# QDRII_power.net
KiCad netlist of a schematic drawn in Altium Designer
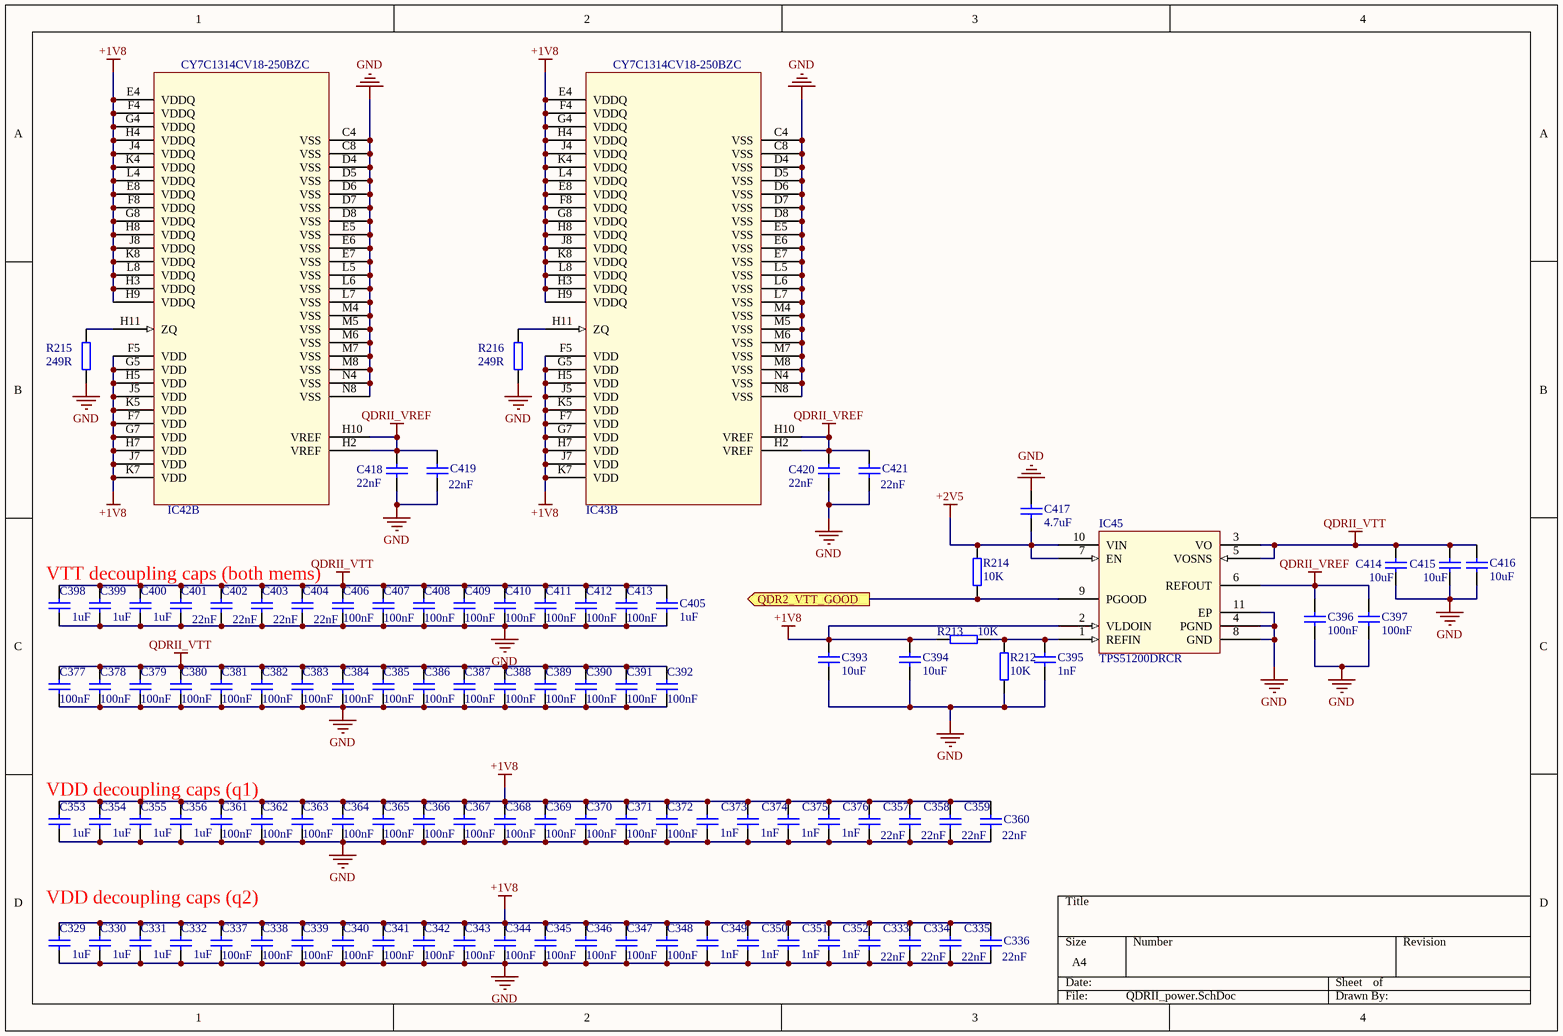
[diagram p0: QDRII_power.SchDoc]

(export (version "E")
  (design (tool "Eeschema 10.0.6"))
  (components
    (comp (ref "C329")
      (value "1uF")
      (footprint "CC1005-0402")
      (description "Capacitor")
      (fields
        (field (name "TOLERANCE") "±10%")
        (field (name "VOLTAGE") "16V")
        (field (name "PUBLISHER") "Altium Limited")
      )
      (libsource (lib "wr_switch") (part "Cap"))
    )
    (comp (ref "C330")
      (value "1uF")
      (footprint "CC1005-0402")
      (description "Capacitor")
      (fields
        (field (name "TOLERANCE") "±10%")
        (field (name "VOLTAGE") "16V")
        (field (name "PUBLISHER") "Altium Limited")
      )
      (libsource (lib "wr_switch") (part "Cap"))
    )
    (comp (ref "C331")
      (value "1uF")
      (footprint "CC1005-0402")
      (description "Capacitor")
      (fields
        (field (name "TOLERANCE") "±10%")
        (field (name "VOLTAGE") "16V")
        (field (name "PUBLISHER") "Altium Limited")
      )
      (libsource (lib "wr_switch") (part "Cap"))
    )
    (comp (ref "C332")
      (value "1uF")
      (footprint "CC1005-0402")
      (description "Capacitor")
      (fields
        (field (name "TOLERANCE") "±10%")
        (field (name "VOLTAGE") "16V")
        (field (name "PUBLISHER") "Altium Limited")
      )
      (libsource (lib "wr_switch") (part "Cap"))
    )
    (comp (ref "C333")
      (value "22nF")
      (footprint "CC1005-0402")
      (description "Capacitor")
      (fields
        (field (name "TOLERANCE") "±10%")
        (field (name "VOLTAGE") "25V")
        (field (name "PUBLISHER") "Altium Limited")
      )
      (libsource (lib "wr_switch") (part "Cap"))
    )
    (comp (ref "C334")
      (value "22nF")
      (footprint "CC1005-0402")
      (description "Capacitor")
      (fields
        (field (name "TOLERANCE") "±10%")
        (field (name "VOLTAGE") "25V")
        (field (name "PUBLISHER") "Altium Limited")
      )
      (libsource (lib "wr_switch") (part "Cap"))
    )
    (comp (ref "C335")
      (value "22nF")
      (footprint "CC1005-0402")
      (description "Capacitor")
      (fields
        (field (name "TOLERANCE") "±10%")
        (field (name "VOLTAGE") "25V")
        (field (name "PUBLISHER") "Altium Limited")
      )
      (libsource (lib "wr_switch") (part "Cap"))
    )
    (comp (ref "C336")
      (value "22nF")
      (footprint "CC1005-0402")
      (description "Capacitor")
      (fields
        (field (name "TOLERANCE") "±10%")
        (field (name "VOLTAGE") "25V")
        (field (name "PUBLISHER") "Altium Limited")
      )
      (libsource (lib "wr_switch") (part "Cap"))
    )
    (comp (ref "C337")
      (value "100nF")
      (footprint "CC1005-0402")
      (description "Capacitor")
      (fields
        (field (name "TOLERANCE") "±10%")
        (field (name "VOLTAGE") "16V")
        (field (name "PUBLISHER") "Altium Limited")
      )
      (libsource (lib "wr_switch") (part "Cap"))
    )
    (comp (ref "C338")
      (value "100nF")
      (footprint "CC1005-0402")
      (description "Capacitor")
      (fields
        (field (name "TOLERANCE") "±10%")
        (field (name "VOLTAGE") "16V")
        (field (name "PUBLISHER") "Altium Limited")
      )
      (libsource (lib "wr_switch") (part "Cap"))
    )
    (comp (ref "C339")
      (value "100nF")
      (footprint "CC1005-0402")
      (description "Capacitor")
      (fields
        (field (name "TOLERANCE") "±10%")
        (field (name "VOLTAGE") "16V")
        (field (name "PUBLISHER") "Altium Limited")
      )
      (libsource (lib "wr_switch") (part "Cap"))
    )
    (comp (ref "C340")
      (value "100nF")
      (footprint "CC1005-0402")
      (description "Capacitor")
      (fields
        (field (name "TOLERANCE") "±10%")
        (field (name "VOLTAGE") "16V")
        (field (name "PUBLISHER") "Altium Limited")
      )
      (libsource (lib "wr_switch") (part "Cap"))
    )
    (comp (ref "C341")
      (value "100nF")
      (footprint "CC1005-0402")
      (description "Capacitor")
      (fields
        (field (name "TOLERANCE") "±10%")
        (field (name "VOLTAGE") "16V")
        (field (name "PUBLISHER") "Altium Limited")
      )
      (libsource (lib "wr_switch") (part "Cap"))
    )
    (comp (ref "C342")
      (value "100nF")
      (footprint "CC1005-0402")
      (description "Capacitor")
      (fields
        (field (name "TOLERANCE") "±10%")
        (field (name "VOLTAGE") "16V")
        (field (name "PUBLISHER") "Altium Limited")
      )
      (libsource (lib "wr_switch") (part "Cap"))
    )
    (comp (ref "C343")
      (value "100nF")
      (footprint "CC1005-0402")
      (description "Capacitor")
      (fields
        (field (name "TOLERANCE") "±10%")
        (field (name "VOLTAGE") "16V")
        (field (name "PUBLISHER") "Altium Limited")
      )
      (libsource (lib "wr_switch") (part "Cap"))
    )
    (comp (ref "C344")
      (value "100nF")
      (footprint "CC1005-0402")
      (description "Capacitor")
      (fields
        (field (name "TOLERANCE") "±10%")
        (field (name "VOLTAGE") "16V")
        (field (name "PUBLISHER") "Altium Limited")
      )
      (libsource (lib "wr_switch") (part "Cap"))
    )
    (comp (ref "C345")
      (value "100nF")
      (footprint "CC1005-0402")
      (description "Capacitor")
      (fields
        (field (name "TOLERANCE") "±10%")
        (field (name "VOLTAGE") "16V")
        (field (name "PUBLISHER") "Altium Limited")
      )
      (libsource (lib "wr_switch") (part "Cap"))
    )
    (comp (ref "C346")
      (value "100nF")
      (footprint "CC1005-0402")
      (description "Capacitor")
      (fields
        (field (name "TOLERANCE") "±10%")
        (field (name "VOLTAGE") "16V")
        (field (name "PUBLISHER") "Altium Limited")
      )
      (libsource (lib "wr_switch") (part "Cap"))
    )
    (comp (ref "C347")
      (value "100nF")
      (footprint "CC1005-0402")
      (description "Capacitor")
      (fields
        (field (name "TOLERANCE") "±10%")
        (field (name "VOLTAGE") "16V")
        (field (name "PUBLISHER") "Altium Limited")
      )
      (libsource (lib "wr_switch") (part "Cap"))
    )
    (comp (ref "C348")
      (value "100nF")
      (footprint "CC1005-0402")
      (description "Capacitor")
      (fields
        (field (name "TOLERANCE") "±10%")
        (field (name "VOLTAGE") "16V")
        (field (name "PUBLISHER") "Altium Limited")
      )
      (libsource (lib "wr_switch") (part "Cap"))
    )
    (comp (ref "C349")
      (value "1nF")
      (footprint "CC1005-0402")
      (description "Capacitor")
      (fields
        (field (name "TOLERANCE") "±10%")
        (field (name "VOLTAGE") "25V")
        (field (name "PUBLISHER") "Altium Limited")
      )
      (libsource (lib "wr_switch") (part "Cap"))
    )
    (comp (ref "C350")
      (value "1nF")
      (footprint "CC1005-0402")
      (description "Capacitor")
      (fields
        (field (name "TOLERANCE") "±10%")
        (field (name "VOLTAGE") "25V")
        (field (name "PUBLISHER") "Altium Limited")
      )
      (libsource (lib "wr_switch") (part "Cap"))
    )
    (comp (ref "C351")
      (value "1nF")
      (footprint "CC1005-0402")
      (description "Capacitor")
      (fields
        (field (name "TOLERANCE") "±10%")
        (field (name "VOLTAGE") "25V")
        (field (name "PUBLISHER") "Altium Limited")
      )
      (libsource (lib "wr_switch") (part "Cap"))
    )
    (comp (ref "C352")
      (value "1nF")
      (footprint "CC1005-0402")
      (description "Capacitor")
      (fields
        (field (name "TOLERANCE") "±10%")
        (field (name "VOLTAGE") "25V")
        (field (name "PUBLISHER") "Altium Limited")
      )
      (libsource (lib "wr_switch") (part "Cap"))
    )
    (comp (ref "C353")
      (value "1uF")
      (footprint "CC1005-0402")
      (description "Capacitor")
      (fields
        (field (name "TOLERANCE") "±10%")
        (field (name "VOLTAGE") "16V")
        (field (name "PUBLISHER") "Altium Limited")
      )
      (libsource (lib "wr_switch") (part "Cap"))
    )
    (comp (ref "C354")
      (value "1uF")
      (footprint "CC1005-0402")
      (description "Capacitor")
      (fields
        (field (name "TOLERANCE") "±10%")
        (field (name "VOLTAGE") "16V")
        (field (name "PUBLISHER") "Altium Limited")
      )
      (libsource (lib "wr_switch") (part "Cap"))
    )
    (comp (ref "C355")
      (value "1uF")
      (footprint "CC1005-0402")
      (description "Capacitor")
      (fields
        (field (name "TOLERANCE") "±10%")
        (field (name "VOLTAGE") "16V")
        (field (name "PUBLISHER") "Altium Limited")
      )
      (libsource (lib "wr_switch") (part "Cap"))
    )
    (comp (ref "C356")
      (value "1uF")
      (footprint "CC1005-0402")
      (description "Capacitor")
      (fields
        (field (name "TOLERANCE") "±10%")
        (field (name "VOLTAGE") "16V")
        (field (name "PUBLISHER") "Altium Limited")
      )
      (libsource (lib "wr_switch") (part "Cap"))
    )
    (comp (ref "C357")
      (value "22nF")
      (footprint "CC1005-0402")
      (description "Capacitor")
      (fields
        (field (name "TOLERANCE") "±10%")
        (field (name "VOLTAGE") "25V")
        (field (name "PUBLISHER") "Altium Limited")
      )
      (libsource (lib "wr_switch") (part "Cap"))
    )
    (comp (ref "C358")
      (value "22nF")
      (footprint "CC1005-0402")
      (description "Capacitor")
      (fields
        (field (name "TOLERANCE") "±10%")
        (field (name "VOLTAGE") "25V")
        (field (name "PUBLISHER") "Altium Limited")
      )
      (libsource (lib "wr_switch") (part "Cap"))
    )
    (comp (ref "C359")
      (value "22nF")
      (footprint "CC1005-0402")
      (description "Capacitor")
      (fields
        (field (name "TOLERANCE") "±10%")
        (field (name "VOLTAGE") "25V")
        (field (name "PUBLISHER") "Altium Limited")
      )
      (libsource (lib "wr_switch") (part "Cap"))
    )
    (comp (ref "C360")
      (value "22nF")
      (footprint "CC1005-0402")
      (description "Capacitor")
      (fields
        (field (name "TOLERANCE") "±10%")
        (field (name "VOLTAGE") "25V")
        (field (name "PUBLISHER") "Altium Limited")
      )
      (libsource (lib "wr_switch") (part "Cap"))
    )
    (comp (ref "C361")
      (value "100nF")
      (footprint "CC1005-0402")
      (description "Capacitor")
      (fields
        (field (name "TOLERANCE") "±10%")
        (field (name "VOLTAGE") "16V")
        (field (name "PUBLISHER") "Altium Limited")
      )
      (libsource (lib "wr_switch") (part "Cap"))
    )
    (comp (ref "C362")
      (value "100nF")
      (footprint "CC1005-0402")
      (description "Capacitor")
      (fields
        (field (name "TOLERANCE") "±10%")
        (field (name "VOLTAGE") "16V")
        (field (name "PUBLISHER") "Altium Limited")
      )
      (libsource (lib "wr_switch") (part "Cap"))
    )
    (comp (ref "C363")
      (value "100nF")
      (footprint "CC1005-0402")
      (description "Capacitor")
      (fields
        (field (name "TOLERANCE") "±10%")
        (field (name "VOLTAGE") "16V")
        (field (name "PUBLISHER") "Altium Limited")
      )
      (libsource (lib "wr_switch") (part "Cap"))
    )
    (comp (ref "C364")
      (value "100nF")
      (footprint "CC1005-0402")
      (description "Capacitor")
      (fields
        (field (name "TOLERANCE") "±10%")
        (field (name "VOLTAGE") "16V")
        (field (name "PUBLISHER") "Altium Limited")
      )
      (libsource (lib "wr_switch") (part "Cap"))
    )
    (comp (ref "C365")
      (value "100nF")
      (footprint "CC1005-0402")
      (description "Capacitor")
      (fields
        (field (name "TOLERANCE") "±10%")
        (field (name "VOLTAGE") "16V")
        (field (name "PUBLISHER") "Altium Limited")
      )
      (libsource (lib "wr_switch") (part "Cap"))
    )
    (comp (ref "C366")
      (value "100nF")
      (footprint "CC1005-0402")
      (description "Capacitor")
      (fields
        (field (name "TOLERANCE") "±10%")
        (field (name "VOLTAGE") "16V")
        (field (name "PUBLISHER") "Altium Limited")
      )
      (libsource (lib "wr_switch") (part "Cap"))
    )
    (comp (ref "C367")
      (value "100nF")
      (footprint "CC1005-0402")
      (description "Capacitor")
      (fields
        (field (name "TOLERANCE") "±10%")
        (field (name "VOLTAGE") "16V")
        (field (name "PUBLISHER") "Altium Limited")
      )
      (libsource (lib "wr_switch") (part "Cap"))
    )
    (comp (ref "C368")
      (value "100nF")
      (footprint "CC1005-0402")
      (description "Capacitor")
      (fields
        (field (name "TOLERANCE") "±10%")
        (field (name "VOLTAGE") "16V")
        (field (name "PUBLISHER") "Altium Limited")
      )
      (libsource (lib "wr_switch") (part "Cap"))
    )
    (comp (ref "C369")
      (value "100nF")
      (footprint "CC1005-0402")
      (description "Capacitor")
      (fields
        (field (name "TOLERANCE") "±10%")
        (field (name "VOLTAGE") "16V")
        (field (name "PUBLISHER") "Altium Limited")
      )
      (libsource (lib "wr_switch") (part "Cap"))
    )
    (comp (ref "C370")
      (value "100nF")
      (footprint "CC1005-0402")
      (description "Capacitor")
      (fields
        (field (name "TOLERANCE") "±10%")
        (field (name "VOLTAGE") "16V")
        (field (name "PUBLISHER") "Altium Limited")
      )
      (libsource (lib "wr_switch") (part "Cap"))
    )
    (comp (ref "C371")
      (value "100nF")
      (footprint "CC1005-0402")
      (description "Capacitor")
      (fields
        (field (name "TOLERANCE") "±10%")
        (field (name "VOLTAGE") "16V")
        (field (name "PUBLISHER") "Altium Limited")
      )
      (libsource (lib "wr_switch") (part "Cap"))
    )
    (comp (ref "C372")
      (value "100nF")
      (footprint "CC1005-0402")
      (description "Capacitor")
      (fields
        (field (name "TOLERANCE") "±10%")
        (field (name "VOLTAGE") "16V")
        (field (name "PUBLISHER") "Altium Limited")
      )
      (libsource (lib "wr_switch") (part "Cap"))
    )
    (comp (ref "C373")
      (value "1nF")
      (footprint "CC1005-0402")
      (description "Capacitor")
      (fields
        (field (name "TOLERANCE") "±10%")
        (field (name "VOLTAGE") "25V")
        (field (name "PUBLISHER") "Altium Limited")
      )
      (libsource (lib "wr_switch") (part "Cap"))
    )
    (comp (ref "C374")
      (value "1nF")
      (footprint "CC1005-0402")
      (description "Capacitor")
      (fields
        (field (name "TOLERANCE") "±10%")
        (field (name "VOLTAGE") "25V")
        (field (name "PUBLISHER") "Altium Limited")
      )
      (libsource (lib "wr_switch") (part "Cap"))
    )
    (comp (ref "C375")
      (value "1nF")
      (footprint "CC1005-0402")
      (description "Capacitor")
      (fields
        (field (name "TOLERANCE") "±10%")
        (field (name "VOLTAGE") "25V")
        (field (name "PUBLISHER") "Altium Limited")
      )
      (libsource (lib "wr_switch") (part "Cap"))
    )
    (comp (ref "C376")
      (value "1nF")
      (footprint "CC1005-0402")
      (description "Capacitor")
      (fields
        (field (name "TOLERANCE") "±10%")
        (field (name "VOLTAGE") "25V")
        (field (name "PUBLISHER") "Altium Limited")
      )
      (libsource (lib "wr_switch") (part "Cap"))
    )
    (comp (ref "C377")
      (value "100nF")
      (footprint "CC1005-0402")
      (description "Capacitor")
      (fields
        (field (name "TOLERANCE") "±10%")
        (field (name "VOLTAGE") "16V")
        (field (name "PUBLISHER") "Altium Limited")
      )
      (libsource (lib "wr_switch") (part "Cap"))
    )
    (comp (ref "C378")
      (value "100nF")
      (footprint "CC1005-0402")
      (description "Capacitor")
      (fields
        (field (name "TOLERANCE") "±10%")
        (field (name "VOLTAGE") "16V")
        (field (name "PUBLISHER") "Altium Limited")
      )
      (libsource (lib "wr_switch") (part "Cap"))
    )
    (comp (ref "C379")
      (value "100nF")
      (footprint "CC1005-0402")
      (description "Capacitor")
      (fields
        (field (name "TOLERANCE") "±10%")
        (field (name "VOLTAGE") "16V")
        (field (name "PUBLISHER") "Altium Limited")
      )
      (libsource (lib "wr_switch") (part "Cap"))
    )
    (comp (ref "C380")
      (value "100nF")
      (footprint "CC1005-0402")
      (description "Capacitor")
      (fields
        (field (name "TOLERANCE") "±10%")
        (field (name "VOLTAGE") "16V")
        (field (name "PUBLISHER") "Altium Limited")
      )
      (libsource (lib "wr_switch") (part "Cap"))
    )
    (comp (ref "C381")
      (value "100nF")
      (footprint "CC1005-0402")
      (description "Capacitor")
      (fields
        (field (name "TOLERANCE") "±10%")
        (field (name "VOLTAGE") "16V")
        (field (name "PUBLISHER") "Altium Limited")
      )
      (libsource (lib "wr_switch") (part "Cap"))
    )
    (comp (ref "C382")
      (value "100nF")
      (footprint "CC1005-0402")
      (description "Capacitor")
      (fields
        (field (name "TOLERANCE") "±10%")
        (field (name "VOLTAGE") "16V")
        (field (name "PUBLISHER") "Altium Limited")
      )
      (libsource (lib "wr_switch") (part "Cap"))
    )
    (comp (ref "C383")
      (value "100nF")
      (footprint "CC1005-0402")
      (description "Capacitor")
      (fields
        (field (name "TOLERANCE") "±10%")
        (field (name "VOLTAGE") "16V")
        (field (name "PUBLISHER") "Altium Limited")
      )
      (libsource (lib "wr_switch") (part "Cap"))
    )
    (comp (ref "C384")
      (value "100nF")
      (footprint "CC1005-0402")
      (description "Capacitor")
      (fields
        (field (name "TOLERANCE") "±10%")
        (field (name "VOLTAGE") "16V")
        (field (name "PUBLISHER") "Altium Limited")
      )
      (libsource (lib "wr_switch") (part "Cap"))
    )
    (comp (ref "C385")
      (value "100nF")
      (footprint "CC1005-0402")
      (description "Capacitor")
      (fields
        (field (name "TOLERANCE") "±10%")
        (field (name "VOLTAGE") "16V")
        (field (name "PUBLISHER") "Altium Limited")
      )
      (libsource (lib "wr_switch") (part "Cap"))
    )
    (comp (ref "C386")
      (value "100nF")
      (footprint "CC1005-0402")
      (description "Capacitor")
      (fields
        (field (name "TOLERANCE") "±10%")
        (field (name "VOLTAGE") "16V")
        (field (name "PUBLISHER") "Altium Limited")
      )
      (libsource (lib "wr_switch") (part "Cap"))
    )
    (comp (ref "C387")
      (value "100nF")
      (footprint "CC1005-0402")
      (description "Capacitor")
      (fields
        (field (name "TOLERANCE") "±10%")
        (field (name "VOLTAGE") "16V")
        (field (name "PUBLISHER") "Altium Limited")
      )
      (libsource (lib "wr_switch") (part "Cap"))
    )
    (comp (ref "C388")
      (value "100nF")
      (footprint "CC1005-0402")
      (description "Capacitor")
      (fields
        (field (name "TOLERANCE") "±10%")
        (field (name "VOLTAGE") "16V")
        (field (name "PUBLISHER") "Altium Limited")
      )
      (libsource (lib "wr_switch") (part "Cap"))
    )
    (comp (ref "C389")
      (value "100nF")
      (footprint "CC1005-0402")
      (description "Capacitor")
      (fields
        (field (name "TOLERANCE") "±10%")
        (field (name "VOLTAGE") "16V")
        (field (name "PUBLISHER") "Altium Limited")
      )
      (libsource (lib "wr_switch") (part "Cap"))
    )
    (comp (ref "C390")
      (value "100nF")
      (footprint "CC1005-0402")
      (description "Capacitor")
      (fields
        (field (name "TOLERANCE") "±10%")
        (field (name "VOLTAGE") "16V")
        (field (name "PUBLISHER") "Altium Limited")
      )
      (libsource (lib "wr_switch") (part "Cap"))
    )
    (comp (ref "C391")
      (value "100nF")
      (footprint "CC1005-0402")
      (description "Capacitor")
      (fields
        (field (name "TOLERANCE") "±10%")
        (field (name "VOLTAGE") "16V")
        (field (name "PUBLISHER") "Altium Limited")
      )
      (libsource (lib "wr_switch") (part "Cap"))
    )
    (comp (ref "C392")
      (value "100nF")
      (footprint "CC1005-0402")
      (description "Capacitor")
      (fields
        (field (name "TOLERANCE") "±10%")
        (field (name "VOLTAGE") "16V")
        (field (name "PUBLISHER") "Altium Limited")
      )
      (libsource (lib "wr_switch") (part "Cap"))
    )
    (comp (ref "C393")
      (value "10uF")
      (footprint "CC1608-0603")
      (description "Capacitor")
      (fields
        (field (name "TOLERANCE") "±20%")
        (field (name "VOLTAGE") "6.3V")
        (field (name "PUBLISHER") "Altium Limited")
      )
      (libsource (lib "wr_switch") (part "Cap"))
    )
    (comp (ref "C394")
      (value "10uF")
      (footprint "CC1608-0603")
      (description "Capacitor")
      (fields
        (field (name "TOLERANCE") "±20%")
        (field (name "VOLTAGE") "6.3V")
        (field (name "PUBLISHER") "Altium Limited")
      )
      (libsource (lib "wr_switch") (part "Cap"))
    )
    (comp (ref "C395")
      (value "1nF")
      (footprint "CC1005-0402")
      (description "Capacitor")
      (fields
        (field (name "TOLERANCE") "±10%")
        (field (name "VOLTAGE") "25V")
        (field (name "PUBLISHER") "Altium Limited")
      )
      (libsource (lib "wr_switch") (part "Cap"))
    )
    (comp (ref "C396")
      (value "100nF")
      (footprint "CC1005-0402")
      (description "Capacitor")
      (fields
        (field (name "TOLERANCE") "±10%")
        (field (name "VOLTAGE") "16V")
        (field (name "PUBLISHER") "Altium Limited")
      )
      (libsource (lib "wr_switch") (part "Cap"))
    )
    (comp (ref "C397")
      (value "100nF")
      (footprint "CC1005-0402")
      (description "Capacitor")
      (fields
        (field (name "TOLERANCE") "±10%")
        (field (name "VOLTAGE") "16V")
        (field (name "PUBLISHER") "Altium Limited")
      )
      (libsource (lib "wr_switch") (part "Cap"))
    )
    (comp (ref "C398")
      (value "1uF")
      (footprint "CC1005-0402")
      (description "Capacitor")
      (fields
        (field (name "TOLERANCE") "±10%")
        (field (name "VOLTAGE") "16V")
        (field (name "PUBLISHER") "Altium Limited")
      )
      (libsource (lib "wr_switch") (part "Cap"))
    )
    (comp (ref "C399")
      (value "1uF")
      (footprint "CC1005-0402")
      (description "Capacitor")
      (fields
        (field (name "TOLERANCE") "±10%")
        (field (name "VOLTAGE") "16V")
        (field (name "PUBLISHER") "Altium Limited")
      )
      (libsource (lib "wr_switch") (part "Cap"))
    )
    (comp (ref "C400")
      (value "1uF")
      (footprint "CC1005-0402")
      (description "Capacitor")
      (fields
        (field (name "TOLERANCE") "±10%")
        (field (name "VOLTAGE") "16V")
        (field (name "PUBLISHER") "Altium Limited")
      )
      (libsource (lib "wr_switch") (part "Cap"))
    )
    (comp (ref "C401")
      (value "22nF")
      (footprint "CC1005-0402")
      (description "Capacitor")
      (fields
        (field (name "TOLERANCE") "±10%")
        (field (name "VOLTAGE") "25V")
        (field (name "PUBLISHER") "Altium Limited")
      )
      (libsource (lib "wr_switch") (part "Cap"))
    )
    (comp (ref "C402")
      (value "22nF")
      (footprint "CC1005-0402")
      (description "Capacitor")
      (fields
        (field (name "TOLERANCE") "±10%")
        (field (name "VOLTAGE") "25V")
        (field (name "PUBLISHER") "Altium Limited")
      )
      (libsource (lib "wr_switch") (part "Cap"))
    )
    (comp (ref "C403")
      (value "22nF")
      (footprint "CC1005-0402")
      (description "Capacitor")
      (fields
        (field (name "TOLERANCE") "±10%")
        (field (name "VOLTAGE") "25V")
        (field (name "PUBLISHER") "Altium Limited")
      )
      (libsource (lib "wr_switch") (part "Cap"))
    )
    (comp (ref "C404")
      (value "22nF")
      (footprint "CC1005-0402")
      (description "Capacitor")
      (fields
        (field (name "TOLERANCE") "±10%")
        (field (name "VOLTAGE") "25V")
        (field (name "PUBLISHER") "Altium Limited")
      )
      (libsource (lib "wr_switch") (part "Cap"))
    )
    (comp (ref "C405")
      (value "1uF")
      (footprint "CC1005-0402")
      (description "Capacitor")
      (fields
        (field (name "TOLERANCE") "±10%")
        (field (name "VOLTAGE") "16V")
        (field (name "PUBLISHER") "Altium Limited")
      )
      (libsource (lib "wr_switch") (part "Cap"))
    )
    (comp (ref "C406")
      (value "100nF")
      (footprint "CC1005-0402")
      (description "Capacitor")
      (fields
        (field (name "TOLERANCE") "±10%")
        (field (name "VOLTAGE") "16V")
        (field (name "PUBLISHER") "Altium Limited")
      )
      (libsource (lib "wr_switch") (part "Cap"))
    )
    (comp (ref "C407")
      (value "100nF")
      (footprint "CC1005-0402")
      (description "Capacitor")
      (fields
        (field (name "TOLERANCE") "±10%")
        (field (name "VOLTAGE") "16V")
        (field (name "PUBLISHER") "Altium Limited")
      )
      (libsource (lib "wr_switch") (part "Cap"))
    )
    (comp (ref "C408")
      (value "100nF")
      (footprint "CC1005-0402")
      (description "Capacitor")
      (fields
        (field (name "TOLERANCE") "±10%")
        (field (name "VOLTAGE") "16V")
        (field (name "PUBLISHER") "Altium Limited")
      )
      (libsource (lib "wr_switch") (part "Cap"))
    )
    (comp (ref "C409")
      (value "100nF")
      (footprint "CC1005-0402")
      (description "Capacitor")
      (fields
        (field (name "TOLERANCE") "±10%")
        (field (name "VOLTAGE") "16V")
        (field (name "PUBLISHER") "Altium Limited")
      )
      (libsource (lib "wr_switch") (part "Cap"))
    )
    (comp (ref "C410")
      (value "100nF")
      (footprint "CC1005-0402")
      (description "Capacitor")
      (fields
        (field (name "TOLERANCE") "±10%")
        (field (name "VOLTAGE") "16V")
        (field (name "PUBLISHER") "Altium Limited")
      )
      (libsource (lib "wr_switch") (part "Cap"))
    )
    (comp (ref "C411")
      (value "100nF")
      (footprint "CC1005-0402")
      (description "Capacitor")
      (fields
        (field (name "TOLERANCE") "±10%")
        (field (name "VOLTAGE") "16V")
        (field (name "PUBLISHER") "Altium Limited")
      )
      (libsource (lib "wr_switch") (part "Cap"))
    )
    (comp (ref "C412")
      (value "100nF")
      (footprint "CC1005-0402")
      (description "Capacitor")
      (fields
        (field (name "TOLERANCE") "±10%")
        (field (name "VOLTAGE") "16V")
        (field (name "PUBLISHER") "Altium Limited")
      )
      (libsource (lib "wr_switch") (part "Cap"))
    )
    (comp (ref "C413")
      (value "100nF")
      (footprint "CC1005-0402")
      (description "Capacitor")
      (fields
        (field (name "TOLERANCE") "±10%")
        (field (name "VOLTAGE") "16V")
        (field (name "PUBLISHER") "Altium Limited")
      )
      (libsource (lib "wr_switch") (part "Cap"))
    )
    (comp (ref "C414")
      (value "10uF")
      (footprint "CC1608-0603")
      (description "Capacitor")
      (fields
        (field (name "TOLERANCE") "±20%")
        (field (name "VOLTAGE") "6.3V")
        (field (name "PUBLISHER") "Altium Limited")
      )
      (libsource (lib "wr_switch") (part "Cap"))
    )
    (comp (ref "C415")
      (value "10uF")
      (footprint "CC1608-0603")
      (description "Capacitor")
      (fields
        (field (name "TOLERANCE") "±20%")
        (field (name "VOLTAGE") "6.3V")
        (field (name "PUBLISHER") "Altium Limited")
      )
      (libsource (lib "wr_switch") (part "Cap"))
    )
    (comp (ref "C416")
      (value "10uF")
      (footprint "CC1608-0603")
      (description "Capacitor")
      (fields
        (field (name "TOLERANCE") "±20%")
        (field (name "VOLTAGE") "6.3V")
        (field (name "PUBLISHER") "Altium Limited")
      )
      (libsource (lib "wr_switch") (part "Cap"))
    )
    (comp (ref "C417")
      (value "4.7uF")
      (footprint "CC1608-0603")
      (description "Capacitor")
      (fields
        (field (name "TOLERANCE") "±10%")
        (field (name "VOLTAGE") "10V")
        (field (name "PUBLISHER") "Altium Limited")
      )
      (libsource (lib "wr_switch") (part "Cap"))
    )
    (comp (ref "C418")
      (value "22nF")
      (footprint "CC1005-0402")
      (description "Capacitor")
      (fields
        (field (name "TOLERANCE") "±10%")
        (field (name "VOLTAGE") "25V")
        (field (name "PUBLISHER") "Altium Limited")
      )
      (libsource (lib "wr_switch") (part "Cap"))
    )
    (comp (ref "C419")
      (value "22nF")
      (footprint "CC1005-0402")
      (description "Capacitor")
      (fields
        (field (name "TOLERANCE") "±10%")
        (field (name "VOLTAGE") "25V")
        (field (name "PUBLISHER") "Altium Limited")
      )
      (libsource (lib "wr_switch") (part "Cap"))
    )
    (comp (ref "C420")
      (value "22nF")
      (footprint "CC1005-0402")
      (description "Capacitor")
      (fields
        (field (name "TOLERANCE") "±10%")
        (field (name "VOLTAGE") "25V")
        (field (name "PUBLISHER") "Altium Limited")
      )
      (libsource (lib "wr_switch") (part "Cap"))
    )
    (comp (ref "C421")
      (value "22nF")
      (footprint "CC1005-0402")
      (description "Capacitor")
      (fields
        (field (name "TOLERANCE") "±10%")
        (field (name "VOLTAGE") "25V")
        (field (name "PUBLISHER") "Altium Limited")
      )
      (libsource (lib "wr_switch") (part "Cap"))
    )
    (comp (ref "IC42")
      (value "CY7C1314CV18-250BZC")
      (description "18-Mbit (512Kx36) QDRII SRAM 2-Word Burst Architecture")
      (libsource (lib "wr_switch") (part "CY7C1314CV18"))
    )
    (comp (ref "IC43")
      (value "CY7C1314CV18-250BZC")
      (description "18-Mbit (512Kx36) QDRII SRAM 2-Word Burst Architecture")
      (libsource (lib "wr_switch") (part "CY7C1314CV18"))
    )
    (comp (ref "IC45")
      (value "TPS51200DRCR")
      (footprint "SON50P300X300X100-11N-R175X250")
      (description "Sink/Source DDR Termination Regulator")
      (libsource (lib "wr_switch") (part "TPS51200"))
    )
    (comp (ref "R212")
      (value "10K")
      (footprint "0402")
      (description "SMD Resistor")
      (fields (field (name "TOLERANCE") "±1%") (field (name "Comment") "10k"))
      (libsource (lib "wr_switch") (part "RES_SMD"))
    )
    (comp (ref "R213")
      (value "10K")
      (footprint "0402")
      (description "SMD Resistor")
      (fields (field (name "TOLERANCE") "±1%") (field (name "Comment") "10k"))
      (libsource (lib "wr_switch") (part "RES_SMD"))
    )
    (comp (ref "R214")
      (value "10K")
      (footprint "0402")
      (description "SMD Resistor")
      (fields (field (name "TOLERANCE") "±1%") (field (name "Comment") "10k"))
      (libsource (lib "wr_switch") (part "RES_SMD"))
    )
    (comp (ref "R215")
      (value "249R")
      (footprint "0402")
      (description "SMD Resistor")
      (fields (field (name "TOLERANCE") "±1%"))
      (libsource (lib "wr_switch") (part "RES_SMD"))
    )
    (comp (ref "R216")
      (value "249R")
      (footprint "0402")
      (description "SMD Resistor")
      (fields (field (name "TOLERANCE") "±1%"))
      (libsource (lib "wr_switch") (part "RES_SMD"))
    )
  )
  (nets
    (net (code "1") (name "+1V8") (class "Default")
      (node (ref "C329") (pin "2") (pinfunction "2_2") (pintype "passive"))
      (node (ref "C330") (pin "2") (pinfunction "2_2") (pintype "passive"))
      (node (ref "C331") (pin "2") (pinfunction "2_2") (pintype "passive"))
      (node (ref "C332") (pin "2") (pinfunction "2_2") (pintype "passive"))
      (node (ref "C333") (pin "2") (pinfunction "2_2") (pintype "passive"))
      (node (ref "C334") (pin "2") (pinfunction "2_2") (pintype "passive"))
      (node (ref "C335") (pin "2") (pinfunction "2_2") (pintype "passive"))
      (node (ref "C336") (pin "2") (pinfunction "2_2") (pintype "passive"))
      (node (ref "C337") (pin "1") (pinfunction "1_1") (pintype "passive"))
      (node (ref "C338") (pin "1") (pinfunction "1_1") (pintype "passive"))
      (node (ref "C339") (pin "1") (pinfunction "1_1") (pintype "passive"))
      (node (ref "C340") (pin "1") (pinfunction "1_1") (pintype "passive"))
      (node (ref "C341") (pin "1") (pinfunction "1_1") (pintype "passive"))
      (node (ref "C342") (pin "1") (pinfunction "1_1") (pintype "passive"))
      (node (ref "C343") (pin "1") (pinfunction "1_1") (pintype "passive"))
      (node (ref "C344") (pin "1") (pinfunction "1_1") (pintype "passive"))
      (node (ref "C345") (pin "1") (pinfunction "1_1") (pintype "passive"))
      (node (ref "C346") (pin "1") (pinfunction "1_1") (pintype "passive"))
      (node (ref "C347") (pin "1") (pinfunction "1_1") (pintype "passive"))
      (node (ref "C348") (pin "1") (pinfunction "1_1") (pintype "passive"))
      (node (ref "C349") (pin "2") (pinfunction "2_2") (pintype "passive"))
      (node (ref "C350") (pin "2") (pinfunction "2_2") (pintype "passive"))
      (node (ref "C351") (pin "2") (pinfunction "2_2") (pintype "passive"))
      (node (ref "C352") (pin "2") (pinfunction "2_2") (pintype "passive"))
      (node (ref "C353") (pin "2") (pinfunction "2_2") (pintype "passive"))
      (node (ref "C354") (pin "2") (pinfunction "2_2") (pintype "passive"))
      (node (ref "C355") (pin "2") (pinfunction "2_2") (pintype "passive"))
      (node (ref "C356") (pin "2") (pinfunction "2_2") (pintype "passive"))
      (node (ref "C357") (pin "2") (pinfunction "2_2") (pintype "passive"))
      (node (ref "C358") (pin "2") (pinfunction "2_2") (pintype "passive"))
      (node (ref "C359") (pin "2") (pinfunction "2_2") (pintype "passive"))
      (node (ref "C360") (pin "2") (pinfunction "2_2") (pintype "passive"))
      (node (ref "C361") (pin "1") (pinfunction "1_1") (pintype "passive"))
      (node (ref "C362") (pin "1") (pinfunction "1_1") (pintype "passive"))
      (node (ref "C363") (pin "1") (pinfunction "1_1") (pintype "passive"))
      (node (ref "C364") (pin "1") (pinfunction "1_1") (pintype "passive"))
      (node (ref "C365") (pin "1") (pinfunction "1_1") (pintype "passive"))
      (node (ref "C366") (pin "1") (pinfunction "1_1") (pintype "passive"))
      (node (ref "C367") (pin "1") (pinfunction "1_1") (pintype "passive"))
      (node (ref "C368") (pin "1") (pinfunction "1_1") (pintype "passive"))
      (node (ref "C369") (pin "1") (pinfunction "1_1") (pintype "passive"))
      (node (ref "C370") (pin "1") (pinfunction "1_1") (pintype "passive"))
      (node (ref "C371") (pin "1") (pinfunction "1_1") (pintype "passive"))
      (node (ref "C372") (pin "1") (pinfunction "1_1") (pintype "passive"))
      (node (ref "C373") (pin "2") (pinfunction "2_2") (pintype "passive"))
      (node (ref "C374") (pin "2") (pinfunction "2_2") (pintype "passive"))
      (node (ref "C375") (pin "2") (pinfunction "2_2") (pintype "passive"))
      (node (ref "C376") (pin "2") (pinfunction "2_2") (pintype "passive"))
      (node (ref "C393") (pin "2") (pinfunction "2_2") (pintype "passive"))
      (node (ref "C394") (pin "2") (pinfunction "2_2") (pintype "passive"))
      (node (ref "IC42") (pin "E4") (pinfunction "VDDQ_E4") (pintype "power_in"))
      (node (ref "IC42") (pin "E8") (pinfunction "VDDQ_E8") (pintype "power_in"))
      (node (ref "IC42") (pin "F4") (pinfunction "VDDQ_F4") (pintype "power_in"))
      (node (ref "IC42") (pin "F5") (pinfunction "VDD_F5") (pintype "power_in"))
      (node (ref "IC42") (pin "F7") (pinfunction "VDD_F7") (pintype "power_in"))
      (node (ref "IC42") (pin "F8") (pinfunction "VDDQ_F8") (pintype "power_in"))
      (node (ref "IC42") (pin "G4") (pinfunction "VDDQ_G4") (pintype "power_in"))
      (node (ref "IC42") (pin "G5") (pinfunction "VDD_G5") (pintype "power_in"))
      (node (ref "IC42") (pin "G7") (pinfunction "VDD_G7") (pintype "power_in"))
      (node (ref "IC42") (pin "G8") (pinfunction "VDDQ_G8") (pintype "power_in"))
      (node (ref "IC42") (pin "H3") (pinfunction "VDDQ_H3") (pintype "power_in"))
      (node (ref "IC42") (pin "H4") (pinfunction "VDDQ_H4") (pintype "power_in"))
      (node (ref "IC42") (pin "H5") (pinfunction "VDD_H5") (pintype "power_in"))
      (node (ref "IC42") (pin "H7") (pinfunction "VDD_H7") (pintype "power_in"))
      (node (ref "IC42") (pin "H8") (pinfunction "VDDQ_H8") (pintype "power_in"))
      (node (ref "IC42") (pin "H9") (pinfunction "VDDQ_H9") (pintype "power_in"))
      (node (ref "IC42") (pin "J4") (pinfunction "VDDQ_J4") (pintype "power_in"))
      (node (ref "IC42") (pin "J5") (pinfunction "VDD_J5") (pintype "power_in"))
      (node (ref "IC42") (pin "J7") (pinfunction "VDD_J7") (pintype "power_in"))
      (node (ref "IC42") (pin "J8") (pinfunction "VDDQ_J8") (pintype "power_in"))
      (node (ref "IC42") (pin "K4") (pinfunction "VDDQ_K4") (pintype "power_in"))
      (node (ref "IC42") (pin "K5") (pinfunction "VDD_K5") (pintype "power_in"))
      (node (ref "IC42") (pin "K7") (pinfunction "VDD_K7") (pintype "power_in"))
      (node (ref "IC42") (pin "K8") (pinfunction "VDDQ_K8") (pintype "power_in"))
      (node (ref "IC42") (pin "L4") (pinfunction "VDDQ_L4") (pintype "power_in"))
      (node (ref "IC42") (pin "L8") (pinfunction "VDDQ_L8") (pintype "power_in"))
      (node (ref "IC43") (pin "E4") (pinfunction "VDDQ_E4") (pintype "power_in"))
      (node (ref "IC43") (pin "E8") (pinfunction "VDDQ_E8") (pintype "power_in"))
      (node (ref "IC43") (pin "F4") (pinfunction "VDDQ_F4") (pintype "power_in"))
      (node (ref "IC43") (pin "F5") (pinfunction "VDD_F5") (pintype "power_in"))
      (node (ref "IC43") (pin "F7") (pinfunction "VDD_F7") (pintype "power_in"))
      (node (ref "IC43") (pin "F8") (pinfunction "VDDQ_F8") (pintype "power_in"))
      (node (ref "IC43") (pin "G4") (pinfunction "VDDQ_G4") (pintype "power_in"))
      (node (ref "IC43") (pin "G5") (pinfunction "VDD_G5") (pintype "power_in"))
      (node (ref "IC43") (pin "G7") (pinfunction "VDD_G7") (pintype "power_in"))
      (node (ref "IC43") (pin "G8") (pinfunction "VDDQ_G8") (pintype "power_in"))
      (node (ref "IC43") (pin "H3") (pinfunction "VDDQ_H3") (pintype "power_in"))
      (node (ref "IC43") (pin "H4") (pinfunction "VDDQ_H4") (pintype "power_in"))
      (node (ref "IC43") (pin "H5") (pinfunction "VDD_H5") (pintype "power_in"))
      (node (ref "IC43") (pin "H7") (pinfunction "VDD_H7") (pintype "power_in"))
      (node (ref "IC43") (pin "H8") (pinfunction "VDDQ_H8") (pintype "power_in"))
      (node (ref "IC43") (pin "H9") (pinfunction "VDDQ_H9") (pintype "power_in"))
      (node (ref "IC43") (pin "J4") (pinfunction "VDDQ_J4") (pintype "power_in"))
      (node (ref "IC43") (pin "J5") (pinfunction "VDD_J5") (pintype "power_in"))
      (node (ref "IC43") (pin "J7") (pinfunction "VDD_J7") (pintype "power_in"))
      (node (ref "IC43") (pin "J8") (pinfunction "VDDQ_J8") (pintype "power_in"))
      (node (ref "IC43") (pin "K4") (pinfunction "VDDQ_K4") (pintype "power_in"))
      (node (ref "IC43") (pin "K5") (pinfunction "VDD_K5") (pintype "power_in"))
      (node (ref "IC43") (pin "K7") (pinfunction "VDD_K7") (pintype "power_in"))
      (node (ref "IC43") (pin "K8") (pinfunction "VDDQ_K8") (pintype "power_in"))
      (node (ref "IC43") (pin "L4") (pinfunction "VDDQ_L4") (pintype "power_in"))
      (node (ref "IC43") (pin "L8") (pinfunction "VDDQ_L8") (pintype "power_in"))
      (node (ref "IC45") (pin "2") (pinfunction "VLDOIN_2") (pintype "input"))
      (node (ref "R213") (pin "2") (pinfunction "2_2") (pintype "passive"))
    )
    (net (code "2") (name "+2V5") (class "Default")
      (node (ref "C417") (pin "1") (pinfunction "1_1") (pintype "passive"))
      (node (ref "IC45") (pin "10") (pinfunction "VIN_10") (pintype "power_in"))
      (node (ref "IC45") (pin "7") (pinfunction "EN_7") (pintype "input"))
      (node (ref "R214") (pin "2") (pinfunction "2_2") (pintype "passive"))
    )
    (net (code "3") (name "/QDR2_VTT_GOOD") (class "Default")
      (node (ref "IC45") (pin "9") (pinfunction "PGOOD_9") (pintype "open_collector"))
      (node (ref "R214") (pin "1") (pinfunction "1_1") (pintype "passive"))
    )
    (net (code "4") (name "GND") (class "Default")
      (node (ref "C329") (pin "1") (pinfunction "1_1") (pintype "passive"))
      (node (ref "C330") (pin "1") (pinfunction "1_1") (pintype "passive"))
      (node (ref "C331") (pin "1") (pinfunction "1_1") (pintype "passive"))
      (node (ref "C332") (pin "1") (pinfunction "1_1") (pintype "passive"))
      (node (ref "C333") (pin "1") (pinfunction "1_1") (pintype "passive"))
      (node (ref "C334") (pin "1") (pinfunction "1_1") (pintype "passive"))
      (node (ref "C335") (pin "1") (pinfunction "1_1") (pintype "passive"))
      (node (ref "C336") (pin "1") (pinfunction "1_1") (pintype "passive"))
      (node (ref "C337") (pin "2") (pinfunction "2_2") (pintype "passive"))
      (node (ref "C338") (pin "2") (pinfunction "2_2") (pintype "passive"))
      (node (ref "C339") (pin "2") (pinfunction "2_2") (pintype "passive"))
      (node (ref "C340") (pin "2") (pinfunction "2_2") (pintype "passive"))
      (node (ref "C341") (pin "2") (pinfunction "2_2") (pintype "passive"))
      (node (ref "C342") (pin "2") (pinfunction "2_2") (pintype "passive"))
      (node (ref "C343") (pin "2") (pinfunction "2_2") (pintype "passive"))
      (node (ref "C344") (pin "2") (pinfunction "2_2") (pintype "passive"))
      (node (ref "C345") (pin "2") (pinfunction "2_2") (pintype "passive"))
      (node (ref "C346") (pin "2") (pinfunction "2_2") (pintype "passive"))
      (node (ref "C347") (pin "2") (pinfunction "2_2") (pintype "passive"))
      (node (ref "C348") (pin "2") (pinfunction "2_2") (pintype "passive"))
      (node (ref "C349") (pin "1") (pinfunction "1_1") (pintype "passive"))
      (node (ref "C350") (pin "1") (pinfunction "1_1") (pintype "passive"))
      (node (ref "C351") (pin "1") (pinfunction "1_1") (pintype "passive"))
      (node (ref "C352") (pin "1") (pinfunction "1_1") (pintype "passive"))
      (node (ref "C353") (pin "1") (pinfunction "1_1") (pintype "passive"))
      (node (ref "C354") (pin "1") (pinfunction "1_1") (pintype "passive"))
      (node (ref "C355") (pin "1") (pinfunction "1_1") (pintype "passive"))
      (node (ref "C356") (pin "1") (pinfunction "1_1") (pintype "passive"))
      (node (ref "C357") (pin "1") (pinfunction "1_1") (pintype "passive"))
      (node (ref "C358") (pin "1") (pinfunction "1_1") (pintype "passive"))
      (node (ref "C359") (pin "1") (pinfunction "1_1") (pintype "passive"))
      (node (ref "C360") (pin "1") (pinfunction "1_1") (pintype "passive"))
      (node (ref "C361") (pin "2") (pinfunction "2_2") (pintype "passive"))
      (node (ref "C362") (pin "2") (pinfunction "2_2") (pintype "passive"))
      (node (ref "C363") (pin "2") (pinfunction "2_2") (pintype "passive"))
      (node (ref "C364") (pin "2") (pinfunction "2_2") (pintype "passive"))
      (node (ref "C365") (pin "2") (pinfunction "2_2") (pintype "passive"))
      (node (ref "C366") (pin "2") (pinfunction "2_2") (pintype "passive"))
      (node (ref "C367") (pin "2") (pinfunction "2_2") (pintype "passive"))
      (node (ref "C368") (pin "2") (pinfunction "2_2") (pintype "passive"))
      (node (ref "C369") (pin "2") (pinfunction "2_2") (pintype "passive"))
      (node (ref "C370") (pin "2") (pinfunction "2_2") (pintype "passive"))
      (node (ref "C371") (pin "2") (pinfunction "2_2") (pintype "passive"))
      (node (ref "C372") (pin "2") (pinfunction "2_2") (pintype "passive"))
      (node (ref "C373") (pin "1") (pinfunction "1_1") (pintype "passive"))
      (node (ref "C374") (pin "1") (pinfunction "1_1") (pintype "passive"))
      (node (ref "C375") (pin "1") (pinfunction "1_1") (pintype "passive"))
      (node (ref "C376") (pin "1") (pinfunction "1_1") (pintype "passive"))
      (node (ref "C377") (pin "2") (pinfunction "2_2") (pintype "passive"))
      (node (ref "C378") (pin "2") (pinfunction "2_2") (pintype "passive"))
      (node (ref "C379") (pin "2") (pinfunction "2_2") (pintype "passive"))
      (node (ref "C380") (pin "2") (pinfunction "2_2") (pintype "passive"))
      (node (ref "C381") (pin "2") (pinfunction "2_2") (pintype "passive"))
      (node (ref "C382") (pin "2") (pinfunction "2_2") (pintype "passive"))
      (node (ref "C383") (pin "2") (pinfunction "2_2") (pintype "passive"))
      (node (ref "C384") (pin "2") (pinfunction "2_2") (pintype "passive"))
      (node (ref "C385") (pin "2") (pinfunction "2_2") (pintype "passive"))
      (node (ref "C386") (pin "2") (pinfunction "2_2") (pintype "passive"))
      (node (ref "C387") (pin "2") (pinfunction "2_2") (pintype "passive"))
      (node (ref "C388") (pin "2") (pinfunction "2_2") (pintype "passive"))
      (node (ref "C389") (pin "2") (pinfunction "2_2") (pintype "passive"))
      (node (ref "C390") (pin "2") (pinfunction "2_2") (pintype "passive"))
      (node (ref "C391") (pin "2") (pinfunction "2_2") (pintype "passive"))
      (node (ref "C392") (pin "2") (pinfunction "2_2") (pintype "passive"))
      (node (ref "C393") (pin "1") (pinfunction "1_1") (pintype "passive"))
      (node (ref "C394") (pin "1") (pinfunction "1_1") (pintype "passive"))
      (node (ref "C395") (pin "1") (pinfunction "1_1") (pintype "passive"))
      (node (ref "C396") (pin "2") (pinfunction "2_2") (pintype "passive"))
      (node (ref "C397") (pin "2") (pinfunction "2_2") (pintype "passive"))
      (node (ref "C398") (pin "1") (pinfunction "1_1") (pintype "passive"))
      (node (ref "C399") (pin "1") (pinfunction "1_1") (pintype "passive"))
      (node (ref "C400") (pin "1") (pinfunction "1_1") (pintype "passive"))
      (node (ref "C401") (pin "1") (pinfunction "1_1") (pintype "passive"))
      (node (ref "C402") (pin "1") (pinfunction "1_1") (pintype "passive"))
      (node (ref "C403") (pin "1") (pinfunction "1_1") (pintype "passive"))
      (node (ref "C404") (pin "1") (pinfunction "1_1") (pintype "passive"))
      (node (ref "C405") (pin "1") (pinfunction "1_1") (pintype "passive"))
      (node (ref "C406") (pin "2") (pinfunction "2_2") (pintype "passive"))
      (node (ref "C407") (pin "2") (pinfunction "2_2") (pintype "passive"))
      (node (ref "C408") (pin "2") (pinfunction "2_2") (pintype "passive"))
      (node (ref "C409") (pin "2") (pinfunction "2_2") (pintype "passive"))
      (node (ref "C410") (pin "2") (pinfunction "2_2") (pintype "passive"))
      (node (ref "C411") (pin "2") (pinfunction "2_2") (pintype "passive"))
      (node (ref "C412") (pin "2") (pinfunction "2_2") (pintype "passive"))
      (node (ref "C413") (pin "2") (pinfunction "2_2") (pintype "passive"))
      (node (ref "C414") (pin "1") (pinfunction "1_1") (pintype "passive"))
      (node (ref "C415") (pin "1") (pinfunction "1_1") (pintype "passive"))
      (node (ref "C416") (pin "1") (pinfunction "1_1") (pintype "passive"))
      (node (ref "C417") (pin "2") (pinfunction "2_2") (pintype "passive"))
      (node (ref "C418") (pin "1") (pinfunction "1_1") (pintype "passive"))
      (node (ref "C419") (pin "1") (pinfunction "1_1") (pintype "passive"))
      (node (ref "C420") (pin "1") (pinfunction "1_1") (pintype "passive"))
      (node (ref "C421") (pin "1") (pinfunction "1_1") (pintype "passive"))
      (node (ref "IC42") (pin "C4") (pinfunction "VSS_C4") (pintype "power_in"))
      (node (ref "IC42") (pin "C8") (pinfunction "VSS_C8") (pintype "power_in"))
      (node (ref "IC42") (pin "D4") (pinfunction "VSS_D4") (pintype "power_in"))
      (node (ref "IC42") (pin "D5") (pinfunction "VSS_D5") (pintype "power_in"))
      (node (ref "IC42") (pin "D6") (pinfunction "VSS_D6") (pintype "power_in"))
      (node (ref "IC42") (pin "D7") (pinfunction "VSS_D7") (pintype "power_in"))
      (node (ref "IC42") (pin "D8") (pinfunction "VSS_D8") (pintype "power_in"))
      (node (ref "IC42") (pin "E5") (pinfunction "VSS_E5") (pintype "power_in"))
      (node (ref "IC42") (pin "E6") (pinfunction "VSS_E6") (pintype "power_in"))
      (node (ref "IC42") (pin "E7") (pinfunction "VSS_E7") (pintype "power_in"))
      (node (ref "IC42") (pin "L5") (pinfunction "VSS_L5") (pintype "power_in"))
      (node (ref "IC42") (pin "L6") (pinfunction "VSS_L6") (pintype "power_in"))
      (node (ref "IC42") (pin "L7") (pinfunction "VSS_L7") (pintype "power_in"))
      (node (ref "IC42") (pin "M4") (pinfunction "VSS_M4") (pintype "power_in"))
      (node (ref "IC42") (pin "M5") (pinfunction "VSS_M5") (pintype "power_in"))
      (node (ref "IC42") (pin "M6") (pinfunction "VSS_M6") (pintype "power_in"))
      (node (ref "IC42") (pin "M7") (pinfunction "VSS_M7") (pintype "power_in"))
      (node (ref "IC42") (pin "M8") (pinfunction "VSS_M8") (pintype "power_in"))
      (node (ref "IC42") (pin "N4") (pinfunction "VSS_N4") (pintype "power_in"))
      (node (ref "IC42") (pin "N8") (pinfunction "VSS_N8") (pintype "power_in"))
      (node (ref "IC43") (pin "C4") (pinfunction "VSS_C4") (pintype "power_in"))
      (node (ref "IC43") (pin "C8") (pinfunction "VSS_C8") (pintype "power_in"))
      (node (ref "IC43") (pin "D4") (pinfunction "VSS_D4") (pintype "power_in"))
      (node (ref "IC43") (pin "D5") (pinfunction "VSS_D5") (pintype "power_in"))
      (node (ref "IC43") (pin "D6") (pinfunction "VSS_D6") (pintype "power_in"))
      (node (ref "IC43") (pin "D7") (pinfunction "VSS_D7") (pintype "power_in"))
      (node (ref "IC43") (pin "D8") (pinfunction "VSS_D8") (pintype "power_in"))
      (node (ref "IC43") (pin "E5") (pinfunction "VSS_E5") (pintype "power_in"))
      (node (ref "IC43") (pin "E6") (pinfunction "VSS_E6") (pintype "power_in"))
      (node (ref "IC43") (pin "E7") (pinfunction "VSS_E7") (pintype "power_in"))
      (node (ref "IC43") (pin "L5") (pinfunction "VSS_L5") (pintype "power_in"))
      (node (ref "IC43") (pin "L6") (pinfunction "VSS_L6") (pintype "power_in"))
      (node (ref "IC43") (pin "L7") (pinfunction "VSS_L7") (pintype "power_in"))
      (node (ref "IC43") (pin "M4") (pinfunction "VSS_M4") (pintype "power_in"))
      (node (ref "IC43") (pin "M5") (pinfunction "VSS_M5") (pintype "power_in"))
      (node (ref "IC43") (pin "M6") (pinfunction "VSS_M6") (pintype "power_in"))
      (node (ref "IC43") (pin "M7") (pinfunction "VSS_M7") (pintype "power_in"))
      (node (ref "IC43") (pin "M8") (pinfunction "VSS_M8") (pintype "power_in"))
      (node (ref "IC43") (pin "N4") (pinfunction "VSS_N4") (pintype "power_in"))
      (node (ref "IC43") (pin "N8") (pinfunction "VSS_N8") (pintype "power_in"))
      (node (ref "IC45") (pin "11") (pinfunction "EP_11") (pintype "power_in"))
      (node (ref "IC45") (pin "4") (pinfunction "PGND_4") (pintype "power_in"))
      (node (ref "IC45") (pin "8") (pinfunction "GND_8") (pintype "power_in"))
      (node (ref "R212") (pin "1") (pinfunction "1_1") (pintype "passive"))
      (node (ref "R215") (pin "1") (pinfunction "1_1") (pintype "passive"))
      (node (ref "R216") (pin "1") (pinfunction "1_1") (pintype "passive"))
    )
    (net (code "5") (name "Net-(IC42B-ZQ)") (class "Default")
      (node (ref "IC42") (pin "H11") (pinfunction "ZQ_H11") (pintype "input"))
      (node (ref "R215") (pin "2") (pinfunction "2_2") (pintype "passive"))
    )
    (net (code "6") (name "Net-(IC43B-ZQ)") (class "Default")
      (node (ref "IC43") (pin "H11") (pinfunction "ZQ_H11") (pintype "input"))
      (node (ref "R216") (pin "2") (pinfunction "2_2") (pintype "passive"))
    )
    (net (code "7") (name "Net-(IC45-REFIN)") (class "Default")
      (node (ref "C395") (pin "2") (pinfunction "2_2") (pintype "passive"))
      (node (ref "IC45") (pin "1") (pinfunction "REFIN_1") (pintype "input"))
      (node (ref "R212") (pin "2") (pinfunction "2_2") (pintype "passive"))
      (node (ref "R213") (pin "1") (pinfunction "1_1") (pintype "passive"))
    )
    (net (code "8") (name "QDRII_VREF") (class "Default")
      (node (ref "C396") (pin "1") (pinfunction "1_1") (pintype "passive"))
      (node (ref "C397") (pin "1") (pinfunction "1_1") (pintype "passive"))
      (node (ref "C418") (pin "2") (pinfunction "2_2") (pintype "passive"))
      (node (ref "C419") (pin "2") (pinfunction "2_2") (pintype "passive"))
      (node (ref "C420") (pin "2") (pinfunction "2_2") (pintype "passive"))
      (node (ref "C421") (pin "2") (pinfunction "2_2") (pintype "passive"))
      (node (ref "IC42") (pin "H10") (pinfunction "VREF_H10") (pintype "power_in"))
      (node (ref "IC42") (pin "H2") (pinfunction "VREF_H2") (pintype "power_in"))
      (node (ref "IC43") (pin "H10") (pinfunction "VREF_H10") (pintype "power_in"))
      (node (ref "IC43") (pin "H2") (pinfunction "VREF_H2") (pintype "power_in"))
      (node (ref "IC45") (pin "6") (pinfunction "REFOUT_6") (pintype "power_in"))
    )
    (net (code "9") (name "QDRII_VTT") (class "Default")
      (node (ref "C377") (pin "1") (pinfunction "1_1") (pintype "passive"))
      (node (ref "C378") (pin "1") (pinfunction "1_1") (pintype "passive"))
      (node (ref "C379") (pin "1") (pinfunction "1_1") (pintype "passive"))
      (node (ref "C380") (pin "1") (pinfunction "1_1") (pintype "passive"))
      (node (ref "C381") (pin "1") (pinfunction "1_1") (pintype "passive"))
      (node (ref "C382") (pin "1") (pinfunction "1_1") (pintype "passive"))
      (node (ref "C383") (pin "1") (pinfunction "1_1") (pintype "passive"))
      (node (ref "C384") (pin "1") (pinfunction "1_1") (pintype "passive"))
      (node (ref "C385") (pin "1") (pinfunction "1_1") (pintype "passive"))
      (node (ref "C386") (pin "1") (pinfunction "1_1") (pintype "passive"))
      (node (ref "C387") (pin "1") (pinfunction "1_1") (pintype "passive"))
      (node (ref "C388") (pin "1") (pinfunction "1_1") (pintype "passive"))
      (node (ref "C389") (pin "1") (pinfunction "1_1") (pintype "passive"))
      (node (ref "C390") (pin "1") (pinfunction "1_1") (pintype "passive"))
      (node (ref "C391") (pin "1") (pinfunction "1_1") (pintype "passive"))
      (node (ref "C392") (pin "1") (pinfunction "1_1") (pintype "passive"))
      (node (ref "C398") (pin "2") (pinfunction "2_2") (pintype "passive"))
      (node (ref "C399") (pin "2") (pinfunction "2_2") (pintype "passive"))
      (node (ref "C400") (pin "2") (pinfunction "2_2") (pintype "passive"))
      (node (ref "C401") (pin "2") (pinfunction "2_2") (pintype "passive"))
      (node (ref "C402") (pin "2") (pinfunction "2_2") (pintype "passive"))
      (node (ref "C403") (pin "2") (pinfunction "2_2") (pintype "passive"))
      (node (ref "C404") (pin "2") (pinfunction "2_2") (pintype "passive"))
      (node (ref "C405") (pin "2") (pinfunction "2_2") (pintype "passive"))
      (node (ref "C406") (pin "1") (pinfunction "1_1") (pintype "passive"))
      (node (ref "C407") (pin "1") (pinfunction "1_1") (pintype "passive"))
      (node (ref "C408") (pin "1") (pinfunction "1_1") (pintype "passive"))
      (node (ref "C409") (pin "1") (pinfunction "1_1") (pintype "passive"))
      (node (ref "C410") (pin "1") (pinfunction "1_1") (pintype "passive"))
      (node (ref "C411") (pin "1") (pinfunction "1_1") (pintype "passive"))
      (node (ref "C412") (pin "1") (pinfunction "1_1") (pintype "passive"))
      (node (ref "C413") (pin "1") (pinfunction "1_1") (pintype "passive"))
      (node (ref "C414") (pin "2") (pinfunction "2_2") (pintype "passive"))
      (node (ref "C415") (pin "2") (pinfunction "2_2") (pintype "passive"))
      (node (ref "C416") (pin "2") (pinfunction "2_2") (pintype "passive"))
      (node (ref "IC45") (pin "3") (pinfunction "VO_3") (pintype "power_in"))
      (node (ref "IC45") (pin "5") (pinfunction "VOSNS_5") (pintype "input"))
    )
  )
)
